# piezo-preamp-tickler_V0-9a.net
KiCad netlist of a schematic drawn in EAGLE
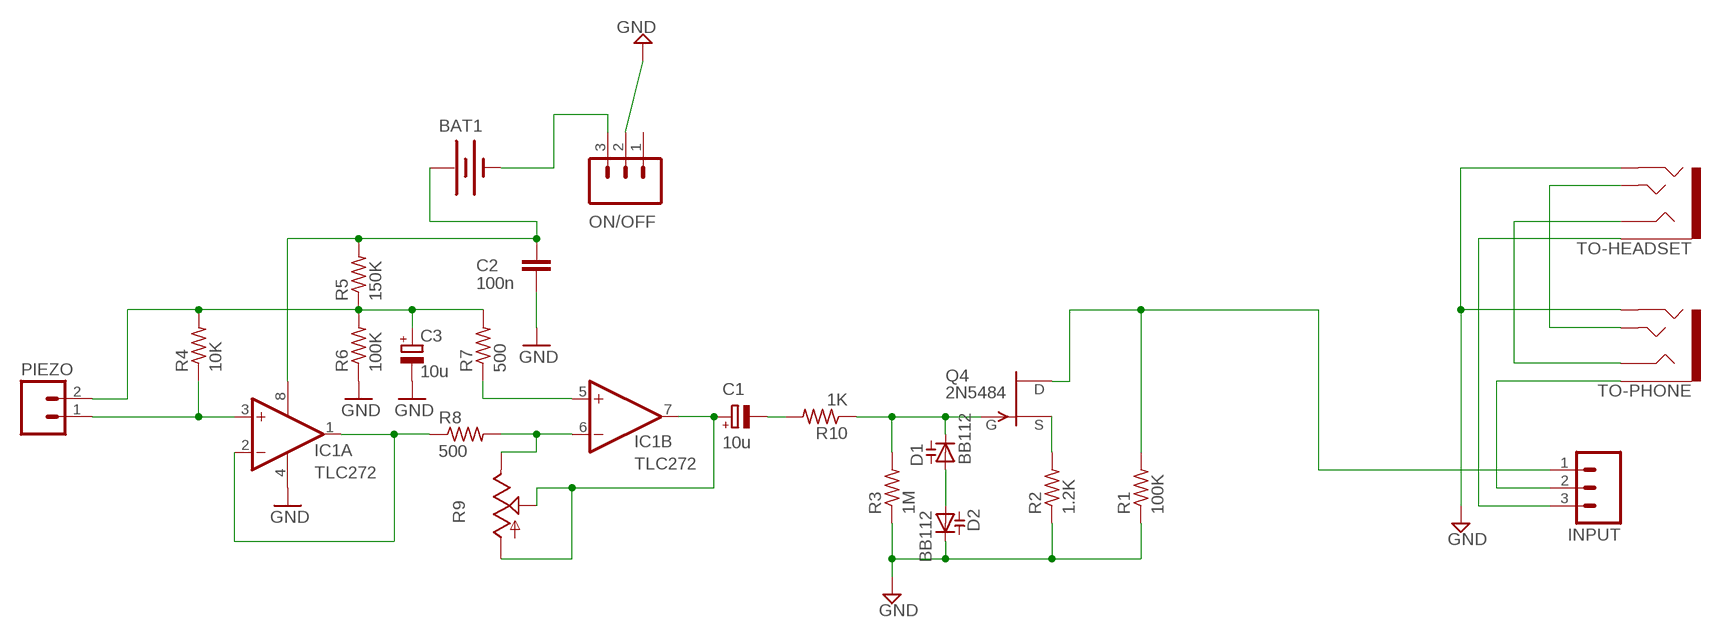
[diagram p0: schematic, sheet 1]

(export (version "E")
  (design (tool "Eeschema 10.0.6"))
  (components
    (comp (ref "BAT1")
      (value "BATTERYA23")
      (footprint "eagle-import:BATTERY-A23")
      (libsource (lib "eagle-import") (part "BATTERYA23"))
    )
    (comp (ref "C1")
      (value "10u")
      (footprint "eagle-import:E2,5-5")
      (libsource (lib "eagle-import") (part "CPOL-EUE2.5-5"))
    )
    (comp (ref "C2")
      (value "100n")
      (footprint "eagle-import:C025-025X050")
      (libsource (lib "eagle-import") (part "C-EU025-025X050"))
    )
    (comp (ref "C3")
      (value "10u")
      (footprint "eagle-import:E2,5-5")
      (libsource (lib "eagle-import") (part "CPOL-EUE2.5-5"))
    )
    (comp (ref "D1")
      (value "BB112")
      (footprint "eagle-import:SOT54H")
      (libsource (lib "eagle-import") (part "BB112"))
    )
    (comp (ref "D2")
      (value "BB112")
      (footprint "eagle-import:SOT54H")
      (libsource (lib "eagle-import") (part "BB112"))
    )
    (comp (ref "IC1")
      (value "TLC272")
      (footprint "eagle-import:DIL08")
      (libsource (lib "eagle-import") (part "TLC272P"))
    )
    (comp (ref "INPUT")
      (value "M03SINGLE-POLE-DOUBLE-THROW")
      (footprint "eagle-import:SPDT-SWITCH")
      (libsource (lib "eagle-import") (part "M03SINGLE-POLE-DOUBLE-THROW"))
    )
    (comp (ref "ON/OFF")
      (value "labl")
      (footprint "eagle-import:SPDT-SWITCH")
      (libsource (lib "eagle-import") (part "M03SINGLE-POLE-DOUBLE-THROW"))
    )
    (comp (ref "PIEZO")
      (value "M02LOCK")
      (footprint "eagle-import:1X02_LOCK")
      (libsource (lib "eagle-import") (part "M02LOCK"))
    )
    (comp (ref "Q4")
      (value "2N5484")
      (footprint "eagle-import:TO92-")
      (libsource (lib "eagle-import") (part "?5482N4"))
    )
    (comp (ref "R1")
      (value "100K")
      (footprint "eagle-import:0204V")
      (libsource (lib "eagle-import") (part "R-US_0204/2V"))
    )
    (comp (ref "R2")
      (value "1.2K")
      (footprint "eagle-import:0204V")
      (libsource (lib "eagle-import") (part "R-US_0204/2V"))
    )
    (comp (ref "R3")
      (value "1M")
      (footprint "eagle-import:0204V")
      (libsource (lib "eagle-import") (part "R-US_0204/2V"))
    )
    (comp (ref "R4")
      (value "10K")
      (footprint "eagle-import:0204V")
      (libsource (lib "eagle-import") (part "R-US_0204/2V"))
    )
    (comp (ref "R5")
      (value "150K")
      (footprint "eagle-import:0204V")
      (libsource (lib "eagle-import") (part "R-US_0204/2V"))
    )
    (comp (ref "R6")
      (value "100K")
      (footprint "eagle-import:0204V")
      (libsource (lib "eagle-import") (part "R-US_0204/2V"))
    )
    (comp (ref "R7")
      (value "500")
      (footprint "eagle-import:0204V")
      (libsource (lib "eagle-import") (part "R-US_0204/2V"))
    )
    (comp (ref "R8")
      (value "500")
      (footprint "eagle-import:0204V")
      (libsource (lib "eagle-import") (part "R-US_0204/2V"))
    )
    (comp (ref "R9")
      (value "TRIM3386")
      (footprint "eagle-import:TRIM-3386")
      (libsource (lib "eagle-import") (part "TRIM3386"))
    )
    (comp (ref "R10")
      (value "1K")
      (footprint "eagle-import:0204V")
      (libsource (lib "eagle-import") (part "R-US_0204/2V"))
    )
    (comp (ref "TO-HEADSET")
      (value "AUDIO-JACK3LGPADS")
      (footprint "eagle-import:AUDIO-JACK-TRRS-SMD")
      (libsource (lib "eagle-import") (part "AUDIO-JACK3LGPADS"))
    )
    (comp (ref "TO-PHONE")
      (value "AUDIO-JACK3LGPADS")
      (footprint "eagle-import:AUDIO-JACK-TRRS-SMD")
      (libsource (lib "eagle-import") (part "AUDIO-JACK3LGPADS"))
    )
  )
  (nets
    (net (code "1") (name "GND") (class "Default")
      (node (ref "C2") (pin "1") (pinfunction "1_1") (pintype "passive"))
      (node (ref "C3") (pin "-") (pinfunction "-_-") (pintype "passive"))
      (node (ref "D2") (pin "C") (pinfunction "C_C") (pintype "passive"))
      (node (ref "IC1") (pin "4") (pinfunction "V-_4") (pintype "power_in"))
      (node (ref "ON/OFF") (pin "2") (pinfunction "2_2") (pintype "passive"))
      (node (ref "R1") (pin "1") (pinfunction "1_1") (pintype "passive"))
      (node (ref "R2") (pin "1") (pinfunction "1_1") (pintype "passive"))
      (node (ref "R3") (pin "1") (pinfunction "1_1") (pintype "passive"))
      (node (ref "R6") (pin "1") (pinfunction "1_1") (pintype "passive"))
      (node (ref "TO-HEADSET") (pin "RING2") (pinfunction "RING2_RING2") (pintype "bidirectional"))
      (node (ref "TO-PHONE") (pin "RING2") (pinfunction "RING2_RING2") (pintype "bidirectional"))
    )
    (net (code "2") (name "Net-(BAT1-+)") (class "Default")
      (node (ref "BAT1") (pin "PWR@1") (pinfunction "+_PWR@1") (pintype "power_in"))
      (node (ref "C2") (pin "2") (pinfunction "2_2") (pintype "passive"))
      (node (ref "IC1") (pin "8") (pinfunction "V+_8") (pintype "power_in"))
      (node (ref "R5") (pin "2") (pinfunction "2_2") (pintype "passive"))
    )
    (net (code "3") (name "Net-(BAT1--)") (class "Default")
      (node (ref "BAT1") (pin "GND@1") (pinfunction "-_GND@1") (pintype "power_in"))
      (node (ref "ON/OFF") (pin "3") (pinfunction "3_3") (pintype "passive"))
    )
    (net (code "4") (name "Net-(C1-Pad-)") (class "Default")
      (node (ref "C1") (pin "-") (pinfunction "-_-") (pintype "passive"))
      (node (ref "R10") (pin "2") (pinfunction "2_2") (pintype "passive"))
    )
    (net (code "5") (name "Net-(C3-Pad+)") (class "Default")
      (node (ref "C3") (pin "+") (pinfunction "+_+") (pintype "passive"))
      (node (ref "PIEZO") (pin "2") (pinfunction "2_2") (pintype "passive"))
      (node (ref "R4") (pin "2") (pinfunction "2_2") (pintype "passive"))
      (node (ref "R5") (pin "1") (pinfunction "1_1") (pintype "passive"))
      (node (ref "R6") (pin "2") (pinfunction "2_2") (pintype "passive"))
      (node (ref "R7") (pin "2") (pinfunction "2_2") (pintype "passive"))
    )
    (net (code "6") (name "Net-(D1-PadA)") (class "Default")
      (node (ref "D1") (pin "A") (pinfunction "A_A") (pintype "passive"))
      (node (ref "D2") (pin "A") (pinfunction "A_A") (pintype "passive"))
    )
    (net (code "7") (name "Net-(IC1A-+IN)") (class "Default")
      (node (ref "IC1") (pin "3") (pinfunction "+IN_3") (pintype "input"))
      (node (ref "PIEZO") (pin "1") (pinfunction "1_1") (pintype "passive"))
      (node (ref "R4") (pin "1") (pinfunction "1_1") (pintype "passive"))
    )
    (net (code "8") (name "Net-(IC1A--IN)") (class "Default")
      (node (ref "IC1") (pin "1") (pinfunction "OUT_1") (pintype "output"))
      (node (ref "IC1") (pin "2") (pinfunction "-IN_2") (pintype "input"))
      (node (ref "R8") (pin "1") (pinfunction "1_1") (pintype "passive"))
    )
    (net (code "9") (name "Net-(IC1B-+IN)") (class "Default")
      (node (ref "IC1") (pin "5") (pinfunction "+IN_5") (pintype "input"))
      (node (ref "R7") (pin "1") (pinfunction "1_1") (pintype "passive"))
    )
    (net (code "10") (name "Net-(IC1B--IN)") (class "Default")
      (node (ref "IC1") (pin "6") (pinfunction "-IN_6") (pintype "input"))
      (node (ref "R8") (pin "2") (pinfunction "2_2") (pintype "passive"))
      (node (ref "R9") (pin "3") (pinfunction "E_3") (pintype "passive"))
      (node (ref "R9") (pin "6") (pinfunction "E_6") (pintype "passive"))
    )
    (net (code "11") (name "Net-(IC1B-OUT)") (class "Default")
      (node (ref "C1") (pin "+") (pinfunction "+_+") (pintype "passive"))
      (node (ref "IC1") (pin "7") (pinfunction "OUT_7") (pintype "output"))
      (node (ref "R9") (pin "1") (pinfunction "A_1") (pintype "passive"))
      (node (ref "R9") (pin "2") (pinfunction "S_2") (pintype "passive"))
      (node (ref "R9") (pin "4") (pinfunction "A_4") (pintype "passive"))
      (node (ref "R9") (pin "5") (pinfunction "S_5") (pintype "passive"))
    )
    (net (code "12") (name "Net-(INPUT-Pad2)") (class "Default")
      (node (ref "INPUT") (pin "2") (pinfunction "2_2") (pintype "passive"))
      (node (ref "TO-PHONE") (pin "EARTH") (pinfunction "EARTH_EARTH") (pintype "bidirectional"))
    )
    (net (code "13") (name "Net-(INPUT-Pad3)") (class "Default")
      (node (ref "INPUT") (pin "3") (pinfunction "3_3") (pintype "passive"))
      (node (ref "TO-HEADSET") (pin "EARTH") (pinfunction "EARTH_EARTH") (pintype "bidirectional"))
    )
    (net (code "14") (name "Net-(Q4-D)") (class "Default")
      (node (ref "INPUT") (pin "1") (pinfunction "1_1") (pintype "passive"))
      (node (ref "Q4") (pin "3") (pinfunction "D_3") (pintype "passive"))
      (node (ref "R1") (pin "2") (pinfunction "2_2") (pintype "passive"))
    )
    (net (code "15") (name "Net-(Q4-G)") (class "Default")
      (node (ref "D1") (pin "C") (pinfunction "C_C") (pintype "passive"))
      (node (ref "Q4") (pin "1") (pinfunction "G_1") (pintype "passive"))
      (node (ref "R10") (pin "1") (pinfunction "1_1") (pintype "passive"))
      (node (ref "R3") (pin "2") (pinfunction "2_2") (pintype "passive"))
    )
    (net (code "16") (name "Net-(Q4-S)") (class "Default")
      (node (ref "Q4") (pin "2") (pinfunction "S_2") (pintype "passive"))
      (node (ref "R2") (pin "2") (pinfunction "2_2") (pintype "passive"))
    )
    (net (code "17") (name "Net-(TO-HEADSET-PadRING1)") (class "Default")
      (node (ref "TO-HEADSET") (pin "RING1") (pinfunction "RING1_RING1") (pintype "bidirectional"))
      (node (ref "TO-PHONE") (pin "RING1") (pinfunction "RING1_RING1") (pintype "bidirectional"))
    )
    (net (code "18") (name "Net-(TO-HEADSET-PadTIP)") (class "Default")
      (node (ref "TO-HEADSET") (pin "TIP") (pinfunction "TIP_TIP") (pintype "bidirectional"))
      (node (ref "TO-PHONE") (pin "TIP") (pinfunction "TIP_TIP") (pintype "bidirectional"))
    )
    (net (code "19") (name "unconnected-(ON/OFF-Pad1)") (class "Default")
      (node (ref "ON/OFF") (pin "1") (pinfunction "1_1") (pintype "passive"))
    )
  )
)
